# PWM_555.net
KiCad netlist of a schematic drawn in EAGLE
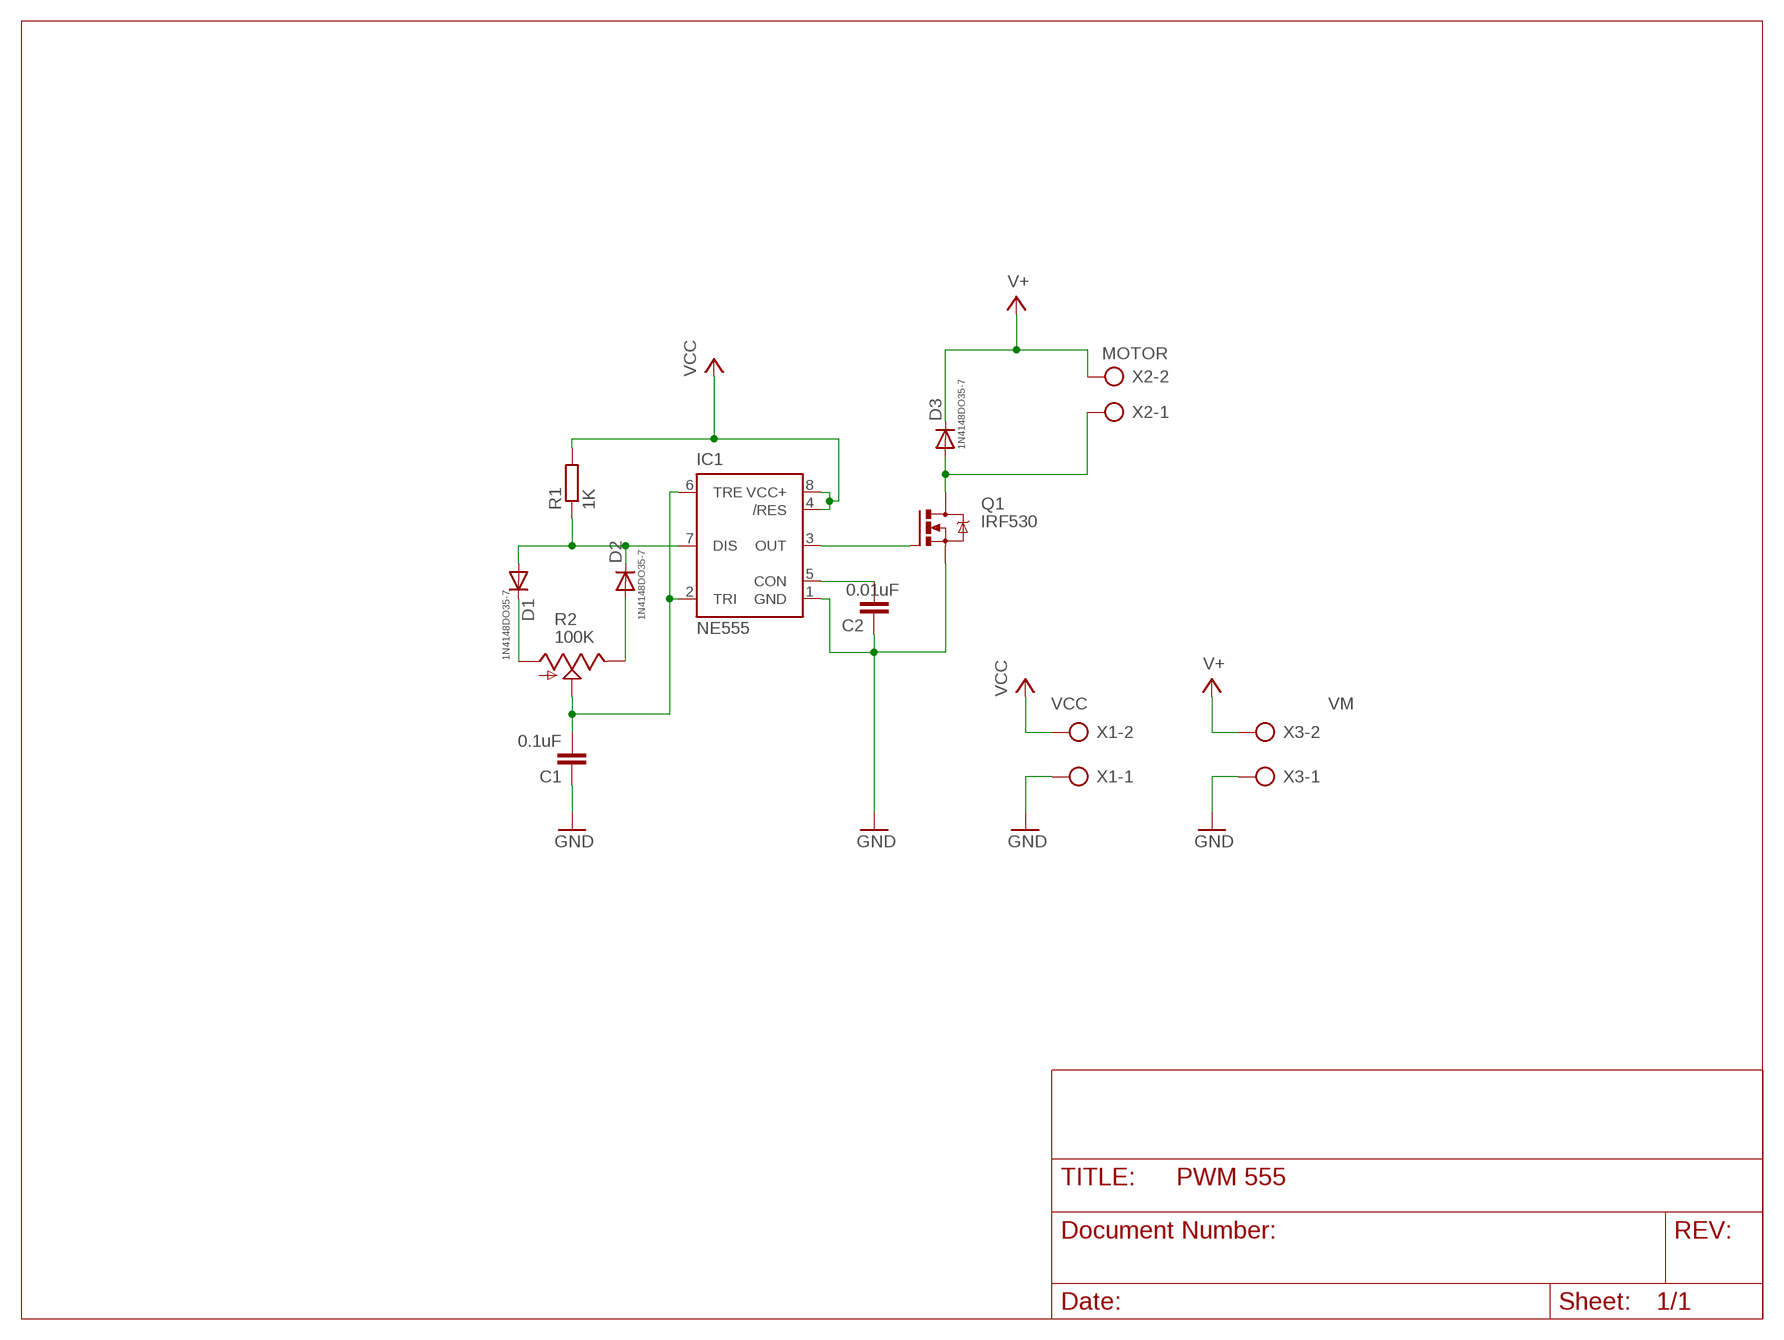
[diagram p0: schematic, sheet 1]

(export (version "E")
  (design (tool "Eeschema 10.0.6"))
  (components
    (comp (ref "C1")
      (value "0.1uF")
      (footprint "eagle-import:C025-024X044")
      (libsource (lib "eagle-import") (part "C-EU025-024X044"))
    )
    (comp (ref "C2")
      (value "0.01uF")
      (footprint "eagle-import:C025-024X044")
      (libsource (lib "eagle-import") (part "C-EU025-024X044"))
    )
    (comp (ref "D1")
      (value "1N4148DO35-7")
      (footprint "eagle-import:DO35-7")
      (libsource (lib "eagle-import") (part "1N4148DO35-7"))
    )
    (comp (ref "D2")
      (value "1N4148DO35-7")
      (footprint "eagle-import:DO35-7")
      (libsource (lib "eagle-import") (part "1N4148DO35-7"))
    )
    (comp (ref "D3")
      (value "1N4148DO35-7")
      (footprint "eagle-import:DO35-7")
      (libsource (lib "eagle-import") (part "1N4148DO35-7"))
    )
    (comp (ref "IC1")
      (value "NE555")
      (footprint "eagle-import:DIL-08")
      (fields (field (name "MF") "Arrow Electronics") (field (name "MPN") "NE555N"))
      (libsource (lib "eagle-import") (part "NE555"))
    )
    (comp (ref "Q1")
      (value "IRF530")
      (footprint "eagle-import:TO220BV")
      (libsource (lib "eagle-import") (part "IRF530"))
    )
    (comp (ref "R1")
      (value "1K")
      (footprint "eagle-import:0207_7")
      (libsource (lib "eagle-import") (part "R-EU_0207/7"))
    )
    (comp (ref "R2")
      (value "100K")
      (footprint "eagle-import:S63S")
      (libsource (lib "eagle-import") (part "TRIM_US-S63S"))
    )
    (comp (ref "X1")
      (value "VCC")
      (footprint "eagle-import:AK500_2-H")
      (libsource (lib "eagle-import") (part "AK500/2-H"))
    )
    (comp (ref "X2")
      (value "MOTOR")
      (footprint "eagle-import:AK500_2-H")
      (libsource (lib "eagle-import") (part "AK500/2-H"))
    )
    (comp (ref "X3")
      (value "VM")
      (footprint "eagle-import:AK500_2-H")
      (libsource (lib "eagle-import") (part "AK500/2-H"))
    )
  )
  (nets
    (net (code "1") (name "GND") (class "Default")
      (node (ref "C1") (pin "1") (pinfunction "1_1") (pintype "passive"))
      (node (ref "C2") (pin "1") (pinfunction "1_1") (pintype "passive"))
      (node (ref "IC1") (pin "1") (pinfunction "GND_1") (pintype "power_in"))
      (node (ref "Q1") (pin "S") (pinfunction "S_S") (pintype "passive"))
      (node (ref "X1") (pin "1") (pinfunction "KL_1") (pintype "passive"))
      (node (ref "X3") (pin "1") (pinfunction "KL_1") (pintype "passive"))
    )
    (net (code "2") (name "Net-(D1-PadC)") (class "Default")
      (node (ref "D1") (pin "C") (pinfunction "C_C") (pintype "passive"))
      (node (ref "R2") (pin "A") (pinfunction "A_A") (pintype "passive"))
    )
    (net (code "3") (name "Net-(D2-PadA)") (class "Default")
      (node (ref "D2") (pin "A") (pinfunction "A_A") (pintype "passive"))
      (node (ref "R2") (pin "E") (pinfunction "E_E") (pintype "passive"))
    )
    (net (code "4") (name "Net-(IC1-CON)") (class "Default")
      (node (ref "C2") (pin "2") (pinfunction "2_2") (pintype "passive"))
      (node (ref "IC1") (pin "5") (pinfunction "CON_5") (pintype "input"))
    )
    (net (code "5") (name "Net-(IC1-DIS)") (class "Default")
      (node (ref "D1") (pin "A") (pinfunction "A_A") (pintype "passive"))
      (node (ref "D2") (pin "C") (pinfunction "C_C") (pintype "passive"))
      (node (ref "IC1") (pin "7") (pinfunction "DIS_7") (pintype "input"))
      (node (ref "R1") (pin "1") (pinfunction "1_1") (pintype "passive"))
    )
    (net (code "6") (name "Net-(IC1-OUT)") (class "Default")
      (node (ref "IC1") (pin "3") (pinfunction "OUT_3") (pintype "output"))
      (node (ref "Q1") (pin "G") (pinfunction "G_G") (pintype "passive"))
    )
    (net (code "7") (name "Net-(IC1-TRE)") (class "Default")
      (node (ref "C1") (pin "2") (pinfunction "2_2") (pintype "passive"))
      (node (ref "IC1") (pin "2") (pinfunction "TRI_2") (pintype "input"))
      (node (ref "IC1") (pin "6") (pinfunction "TRE_6") (pintype "input"))
      (node (ref "R2") (pin "S") (pinfunction "S_S") (pintype "passive"))
    )
    (net (code "8") (name "Net-(X2A-KL)") (class "Default")
      (node (ref "D3") (pin "A") (pinfunction "A_A") (pintype "passive"))
      (node (ref "Q1") (pin "D") (pinfunction "D_D") (pintype "passive"))
      (node (ref "X2") (pin "1") (pinfunction "KL_1") (pintype "passive"))
    )
    (net (code "9") (name "V+") (class "Default")
      (node (ref "D3") (pin "C") (pinfunction "C_C") (pintype "passive"))
      (node (ref "X2") (pin "2") (pinfunction "KL_2") (pintype "passive"))
      (node (ref "X3") (pin "2") (pinfunction "KL_2") (pintype "passive"))
    )
    (net (code "10") (name "VCC") (class "Default")
      (node (ref "IC1") (pin "4") (pinfunction "/RES_4") (pintype "input"))
      (node (ref "IC1") (pin "8") (pinfunction "VCC+_8") (pintype "power_in"))
      (node (ref "R1") (pin "2") (pinfunction "2_2") (pintype "passive"))
      (node (ref "X1") (pin "2") (pinfunction "KL_2") (pintype "passive"))
    )
  )
)
